# motion-detector-easy_eda.net
KiCad netlist of a schematic drawn in EasyEDA
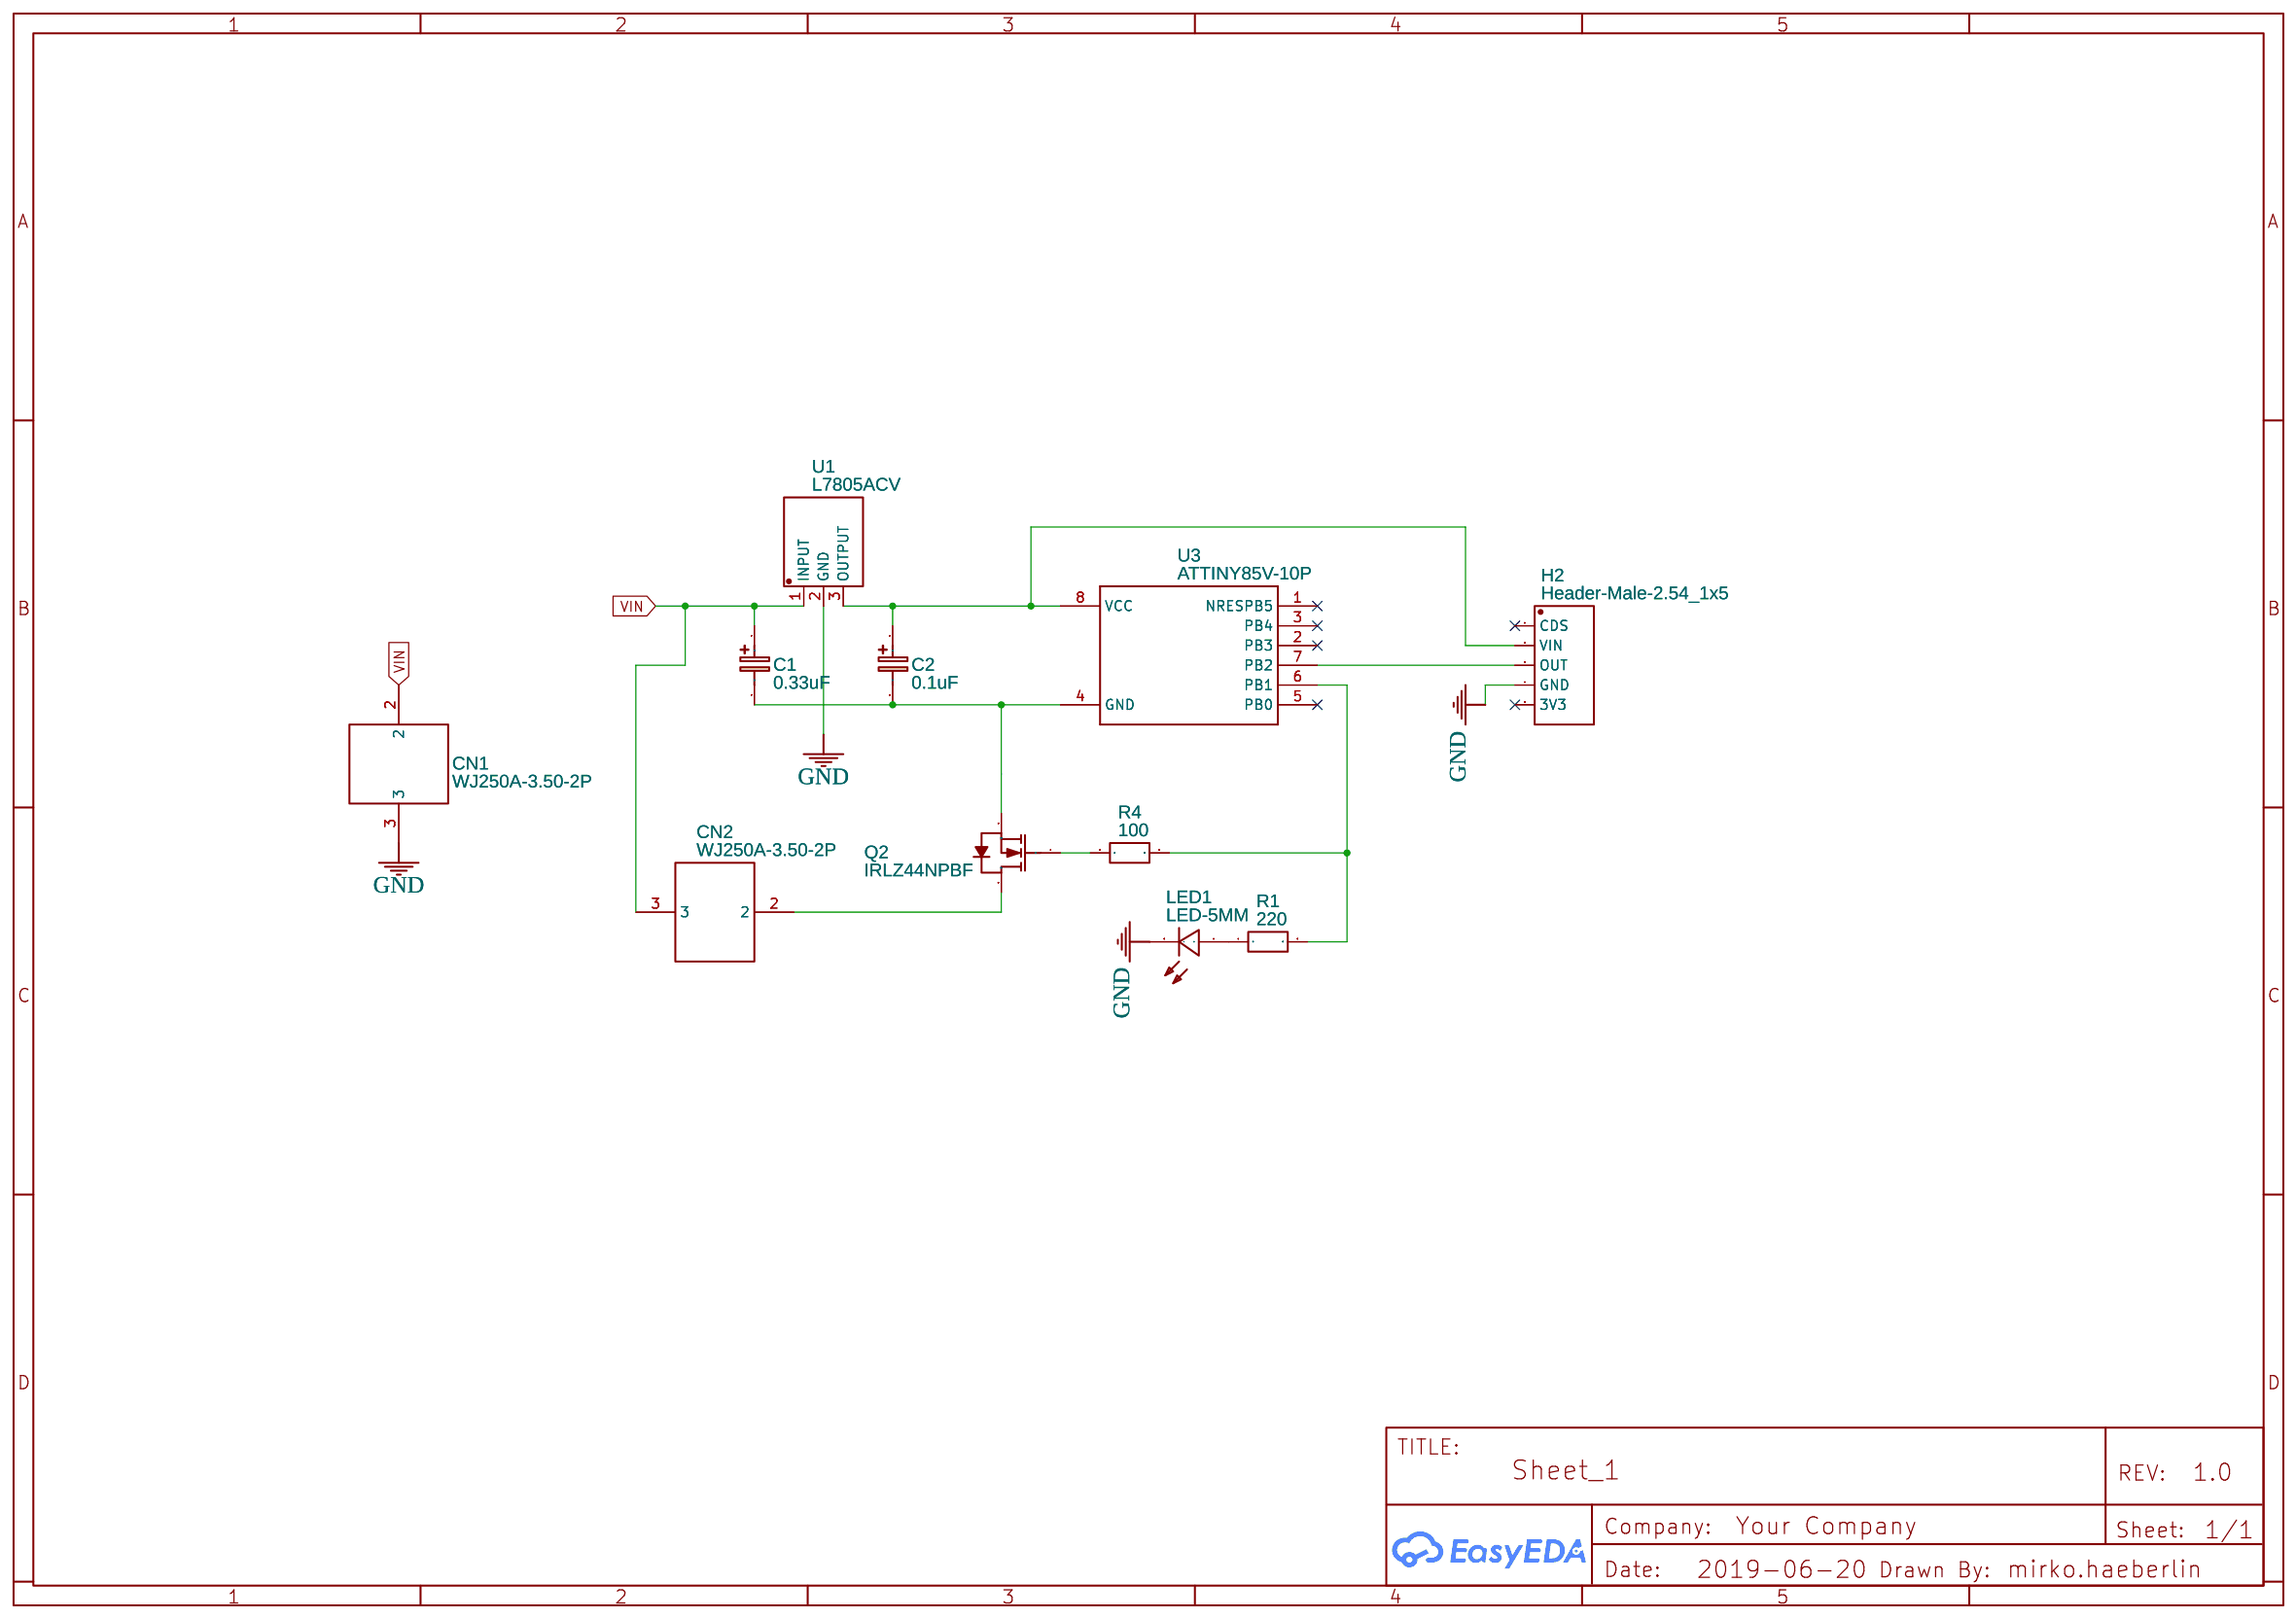
[diagram p0: schematic sheet]

(export (version "E")
  (design (tool "Eeschema 10.0.6"))
  (components
    (comp (ref "C1")
      (value "0.33uF")
      (fields (field (name "BOM_Manufacturer Part") "?"))
      (libsource (lib "") (part "Cap_Electrolytic(TH)_D3.0XF1.5_EU"))
    )
    (comp (ref "C2")
      (value "0.1uF")
      (fields (field (name "BOM_Manufacturer Part") "?"))
      (libsource (lib "") (part "Cap_Electrolytic(TH)_D3.0XF1.5_EU"))
    )
    (comp (ref "CN1")
      (value "WJ250A-3.50-2P")
      (fields (field (name "BOM_Supplier Part") "C8421"))
      (libsource (lib "") (part "Unknown_195_380"))
    )
    (comp (ref "CN2")
      (value "WJ250A-3.50-2P")
      (fields (field (name "BOM_Supplier Part") "C8421"))
      (libsource (lib "") (part "Unknown_355_455"))
    )
    (comp (ref "H2")
      (value "Header-Male-2.54_1x5")
      (fields
        (field (name "BOM_Manufacturer Part") "210S-1*5P L=11.6MMGold-plated black")
        (field (name "BOM_Supplier Part") "C124379")
      )
      (libsource (lib "") (part "Unknown_780_330"))
    )
    (comp (ref "LED1")
      (value "LED-5MM")
      (fields (field (name "BOM_Manufacturer Part") "5AR2ST10") (field (name "BOM_Supplier Part") "C52721"))
      (libsource (lib "") (part "Unknown_595_475"))
    )
    (comp (ref "Q2")
      (value "IRLZ44NPBF")
      (fields (field (name "BOM_Supplier Part") "C38774"))
      (libsource (lib "") (part "Unknown_510_425"))
    )
    (comp (ref "R1")
      (value "220")
      (fields (field (name "BOM_Manufacturer Part") "?"))
      (libsource (lib "") (part "Res_AXIAL-0.4(1/4W)_EU"))
    )
    (comp (ref "R4")
      (value "100")
      (fields (field (name "BOM_Manufacturer Part") "?"))
      (libsource (lib "") (part "Res_AXIAL-0.4(1/4W)_EU"))
    )
    (comp (ref "U1")
      (value "L7805ACV")
      (fields (field (name "BOM_Supplier Part") "C192854"))
      (libsource (lib "") (part "Unknown_410_275"))
    )
    (comp (ref "U3")
      (value "ATTINY85V-10P")
      (fields (field (name "BOM_Manufacturer Part") "?"))
      (libsource (lib "") (part "Unknown_595_325"))
    )
  )
  (nets
    (net (code "1") (name "GND") (class "Default")
      (node (ref "CN1") (pin "3") (pinfunction "3_3") (pintype "unspecified"))
      (node (ref "H2") (pin "4") (pinfunction "GND_4") (pintype "unspecified"))
      (node (ref "LED1") (pin "2") (pinfunction "-_2") (pintype "unspecified"))
      (node (ref "U1") (pin "2") (pinfunction "GND_2") (pintype "unspecified"))
    )
    (net (code "2") (name "Net-(H2-OUT)") (class "Default")
      (node (ref "H2") (pin "3") (pinfunction "OUT_3") (pintype "unspecified"))
      (node (ref "U3") (pin "7") (pinfunction "PB2_7") (pintype "unspecified"))
    )
    (net (code "3") (name "Net-(H2-VIN)") (class "Default")
      (node (ref "C2") (pin "1") (pinfunction "1_1") (pintype "unspecified"))
      (node (ref "H2") (pin "2") (pinfunction "VIN_2") (pintype "unspecified"))
      (node (ref "U1") (pin "3") (pinfunction "OUTPUT_3") (pintype "unspecified"))
      (node (ref "U3") (pin "8") (pinfunction "VCC_8") (pintype "passive"))
    )
    (net (code "4") (name "Net-(LED1-+)") (class "Default")
      (node (ref "LED1") (pin "1") (pinfunction "+_1") (pintype "unspecified"))
      (node (ref "R1") (pin "1") (pinfunction "1_1") (pintype "unspecified"))
    )
    (net (code "5") (name "Net-(Q2-D)") (class "Default")
      (node (ref "CN2") (pin "2") (pinfunction "2_2") (pintype "unspecified"))
      (node (ref "Q2") (pin "2") (pinfunction "D_2") (pintype "unspecified"))
    )
    (net (code "6") (name "Net-(Q2-G)") (class "Default")
      (node (ref "Q2") (pin "1") (pinfunction "G_1") (pintype "unspecified"))
      (node (ref "R4") (pin "1") (pinfunction "1_1") (pintype "unspecified"))
    )
    (net (code "7") (name "Net-(Q2-S)") (class "Default")
      (node (ref "C1") (pin "2") (pinfunction "2_2") (pintype "unspecified"))
      (node (ref "C2") (pin "2") (pinfunction "2_2") (pintype "unspecified"))
      (node (ref "Q2") (pin "3") (pinfunction "S_3") (pintype "unspecified"))
      (node (ref "U3") (pin "4") (pinfunction "GND_4") (pintype "passive"))
    )
    (net (code "8") (name "Net-(U3-PB1)") (class "Default")
      (node (ref "R1") (pin "2") (pinfunction "2_2") (pintype "unspecified"))
      (node (ref "R4") (pin "2") (pinfunction "2_2") (pintype "unspecified"))
      (node (ref "U3") (pin "6") (pinfunction "PB1_6") (pintype "unspecified"))
    )
    (net (code "9") (name "VIN") (class "Default")
      (node (ref "C1") (pin "1") (pinfunction "1_1") (pintype "unspecified"))
      (node (ref "CN1") (pin "2") (pinfunction "2_2") (pintype "unspecified"))
      (node (ref "CN2") (pin "3") (pinfunction "3_3") (pintype "unspecified"))
      (node (ref "U1") (pin "1") (pinfunction "INPUT_1") (pintype "unspecified"))
    )
    (net (code "10") (name "unconnected-(H2-3V3-Pad5)") (class "Default")
      (node (ref "H2") (pin "5") (pinfunction "3V3_5") (pintype "unspecified+no_connect"))
    )
    (net (code "11") (name "unconnected-(H2-CDS-Pad1)") (class "Default")
      (node (ref "H2") (pin "1") (pinfunction "CDS_1") (pintype "unspecified+no_connect"))
    )
    (net (code "12") (name "unconnected-(U3-NRESPB5-Pad1)") (class "Default")
      (node (ref "U3") (pin "1") (pinfunction "NRESPB5_1") (pintype "unspecified+no_connect"))
    )
    (net (code "13") (name "unconnected-(U3-PB0-Pad5)") (class "Default")
      (node (ref "U3") (pin "5") (pinfunction "PB0_5") (pintype "unspecified+no_connect"))
    )
    (net (code "14") (name "unconnected-(U3-PB3-Pad2)") (class "Default")
      (node (ref "U3") (pin "2") (pinfunction "PB3_2") (pintype "unspecified+no_connect"))
    )
    (net (code "15") (name "unconnected-(U3-PB4-Pad3)") (class "Default")
      (node (ref "U3") (pin "3") (pinfunction "PB4_3") (pintype "unspecified+no_connect"))
    )
  )
)
